# Display_V1_1.net
KiCad netlist of a schematic drawn in EAGLE
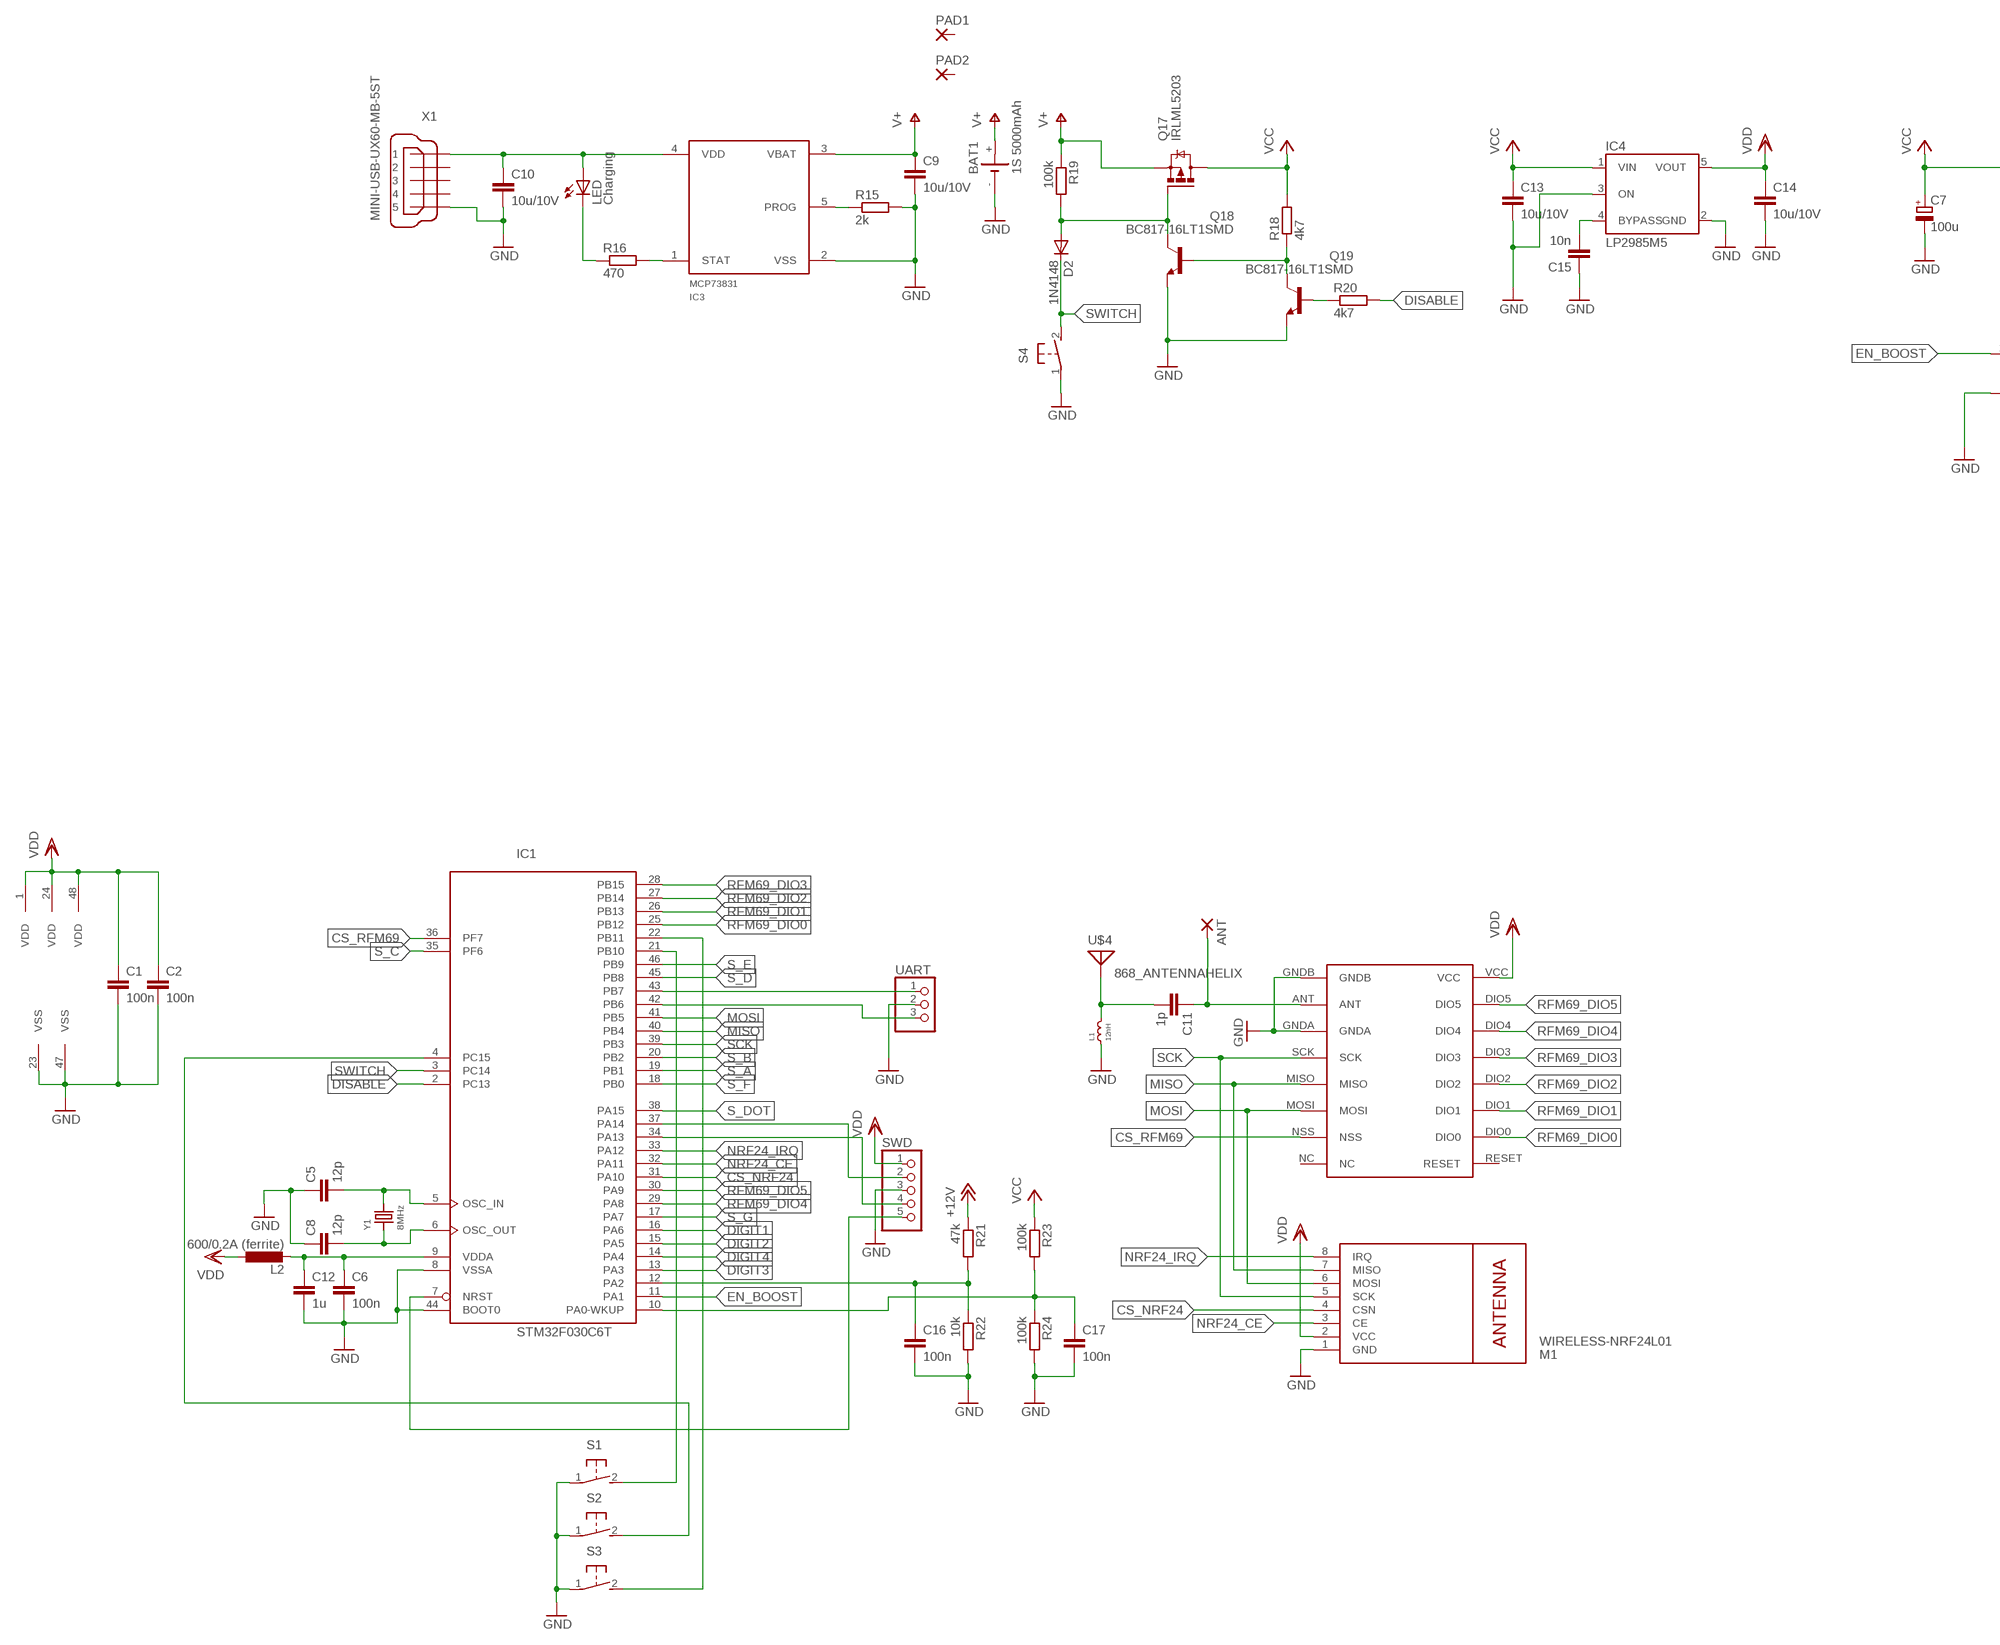
[diagram p0: schematic, sheet 1, part 1 of 2]
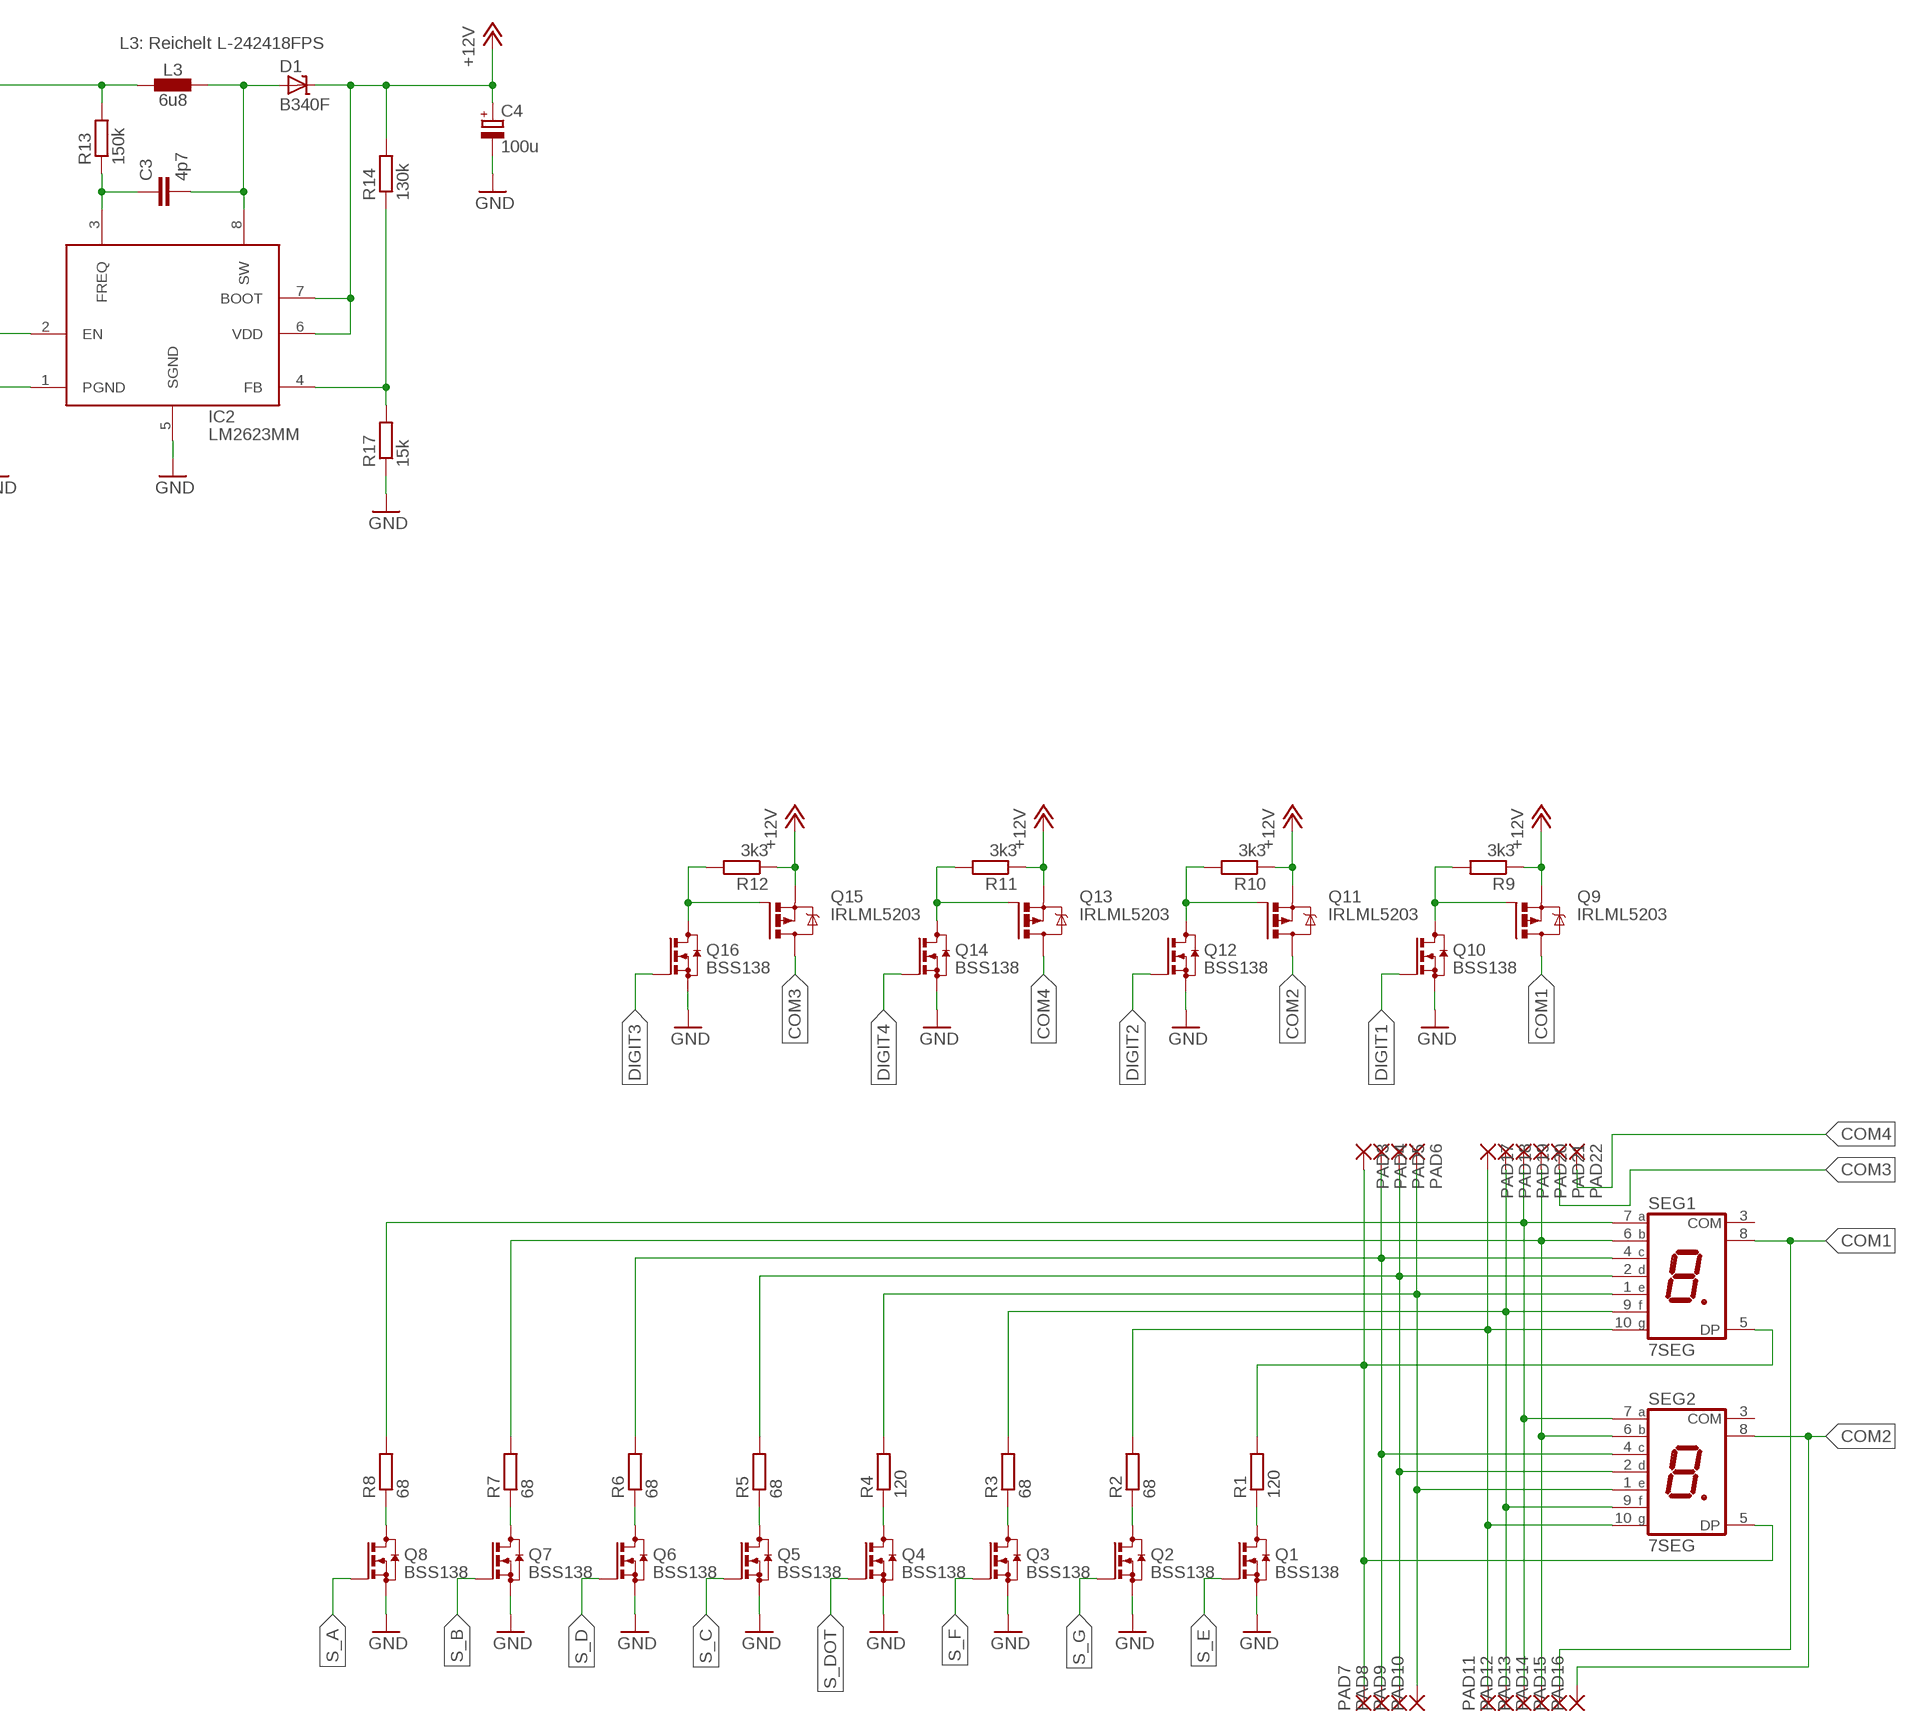
[diagram p1: schematic, sheet 1, part 2 of 2]

(export (version "E")
  (design (tool "Eeschema 10.0.6"))
  (components
    (comp (ref "ANT")
      (value "1,6/0,8")
      (footprint "eagle-import:1,6_0,8")
      (libsource (lib "eagle-import") (part "1,6/0,8"))
    )
    (comp (ref "BAT1")
      (value "1S 5000mAh")
      (footprint "eagle-import:1S_5000MAH")
      (libsource (lib "eagle-import") (part "LIPO"))
    )
    (comp (ref "C1")
      (value "100n")
      (footprint "eagle-import:C0603K")
      (libsource (lib "eagle-import") (part "C-EUC0603K"))
    )
    (comp (ref "C2")
      (value "100n")
      (footprint "eagle-import:C0603K")
      (libsource (lib "eagle-import") (part "C-EUC0603K"))
    )
    (comp (ref "C3")
      (value "4p7")
      (footprint "eagle-import:C0603")
      (libsource (lib "eagle-import") (part "C-EUC0603"))
    )
    (comp (ref "C4")
      (value "100u")
      (footprint "eagle-import:153CLV-0605")
      (libsource (lib "eagle-import") (part "CPOL-EU153CLV-0605"))
    )
    (comp (ref "C5")
      (value "12p")
      (footprint "eagle-import:C0603")
      (libsource (lib "eagle-import") (part "C-EUC0603"))
    )
    (comp (ref "C6")
      (value "100n")
      (footprint "eagle-import:C0603")
      (libsource (lib "eagle-import") (part "C-EUC0603"))
    )
    (comp (ref "C7")
      (value "100u")
      (footprint "eagle-import:153CLV-0605")
      (libsource (lib "eagle-import") (part "CPOL-EU153CLV-0605"))
    )
    (comp (ref "C8")
      (value "12p")
      (footprint "eagle-import:C0603")
      (libsource (lib "eagle-import") (part "C-EUC0603"))
    )
    (comp (ref "C9")
      (value "10u/10V")
      (footprint "eagle-import:C1206")
      (libsource (lib "eagle-import") (part "C-EUC1206"))
    )
    (comp (ref "C10")
      (value "10u/10V")
      (footprint "eagle-import:C1206")
      (libsource (lib "eagle-import") (part "C-EUC1206"))
    )
    (comp (ref "C11")
      (value "1p")
      (footprint "eagle-import:C0603")
      (libsource (lib "eagle-import") (part "C-EUC0603"))
    )
    (comp (ref "C12")
      (value "1u")
      (footprint "eagle-import:C0603")
      (libsource (lib "eagle-import") (part "C-EUC0603"))
    )
    (comp (ref "C13")
      (value "10u/10V")
      (footprint "eagle-import:C1206")
      (libsource (lib "eagle-import") (part "C-EUC1206"))
    )
    (comp (ref "C14")
      (value "10u/10V")
      (footprint "eagle-import:C1206")
      (libsource (lib "eagle-import") (part "C-EUC1206"))
    )
    (comp (ref "C15")
      (value "10n")
      (footprint "eagle-import:C0603")
      (libsource (lib "eagle-import") (part "C-EUC0603"))
    )
    (comp (ref "C16")
      (value "100n")
      (footprint "eagle-import:C0603")
      (libsource (lib "eagle-import") (part "C-EUC0603"))
    )
    (comp (ref "C17")
      (value "100n")
      (footprint "eagle-import:C0603")
      (libsource (lib "eagle-import") (part "C-EUC0603"))
    )
    (comp (ref "D1")
      (value "B340F")
      (footprint "eagle-import:SMC")
      (libsource (lib "eagle-import") (part "SD-SMC"))
    )
    (comp (ref "D2")
      (value "1N4148")
      (footprint "eagle-import:MINIMELF")
      (libsource (lib "eagle-import") (part "DIODE-MINIMELF"))
    )
    (comp (ref "IC1")
      (value "STM32F030C6T")
      (footprint "eagle-import:LQFP48")
      (libsource (lib "eagle-import") (part "STM32F030CT6"))
    )
    (comp (ref "IC2")
      (value "LM2623MM")
      (footprint "eagle-import:MSOP08")
      (libsource (lib "eagle-import") (part "LM2623MM"))
    )
    (comp (ref "IC3")
      (value "MCP73831")
      (footprint "eagle-import:SOT23-5")
      (libsource (lib "eagle-import") (part "MCP73831"))
    )
    (comp (ref "IC4")
      (value "LP2985M5")
      (footprint "eagle-import:SOT23-5")
      (libsource (lib "eagle-import") (part "LP2985M5"))
    )
    (comp (ref "L1")
      (value "12nH")
      (footprint "eagle-import:0603")
      (libsource (lib "eagle-import") (part "RF-INDUCTOR.0603"))
    )
    (comp (ref "L2")
      (value "600/0.2A (ferrite)")
      (footprint "eagle-import:L2012C")
      (libsource (lib "eagle-import") (part "L-EUL2012C"))
    )
    (comp (ref "L3")
      (value "6u8")
      (footprint "eagle-import:L_NR60XX")
      (libsource (lib "eagle-import") (part "INDUCTOR-NR60XX"))
    )
    (comp (ref "LED")
      (value "Charging")
      (footprint "eagle-import:CHIPLED_0603")
      (libsource (lib "eagle-import") (part "LEDCHIPLED_0603"))
    )
    (comp (ref "M1")
      (value "WIRELESS-NRF24L01")
      (footprint "eagle-import:WIRELESS-NRF24L01")
      (libsource (lib "eagle-import") (part "WIRELESS-NRF24L01"))
    )
    (comp (ref "PAD1")
      (value "2,54/1,0")
      (footprint "eagle-import:2,54_1,0")
      (libsource (lib "eagle-import") (part "2,54/1,0"))
    )
    (comp (ref "PAD2")
      (value "2,54/1,0")
      (footprint "eagle-import:2,54_1,0")
      (libsource (lib "eagle-import") (part "2,54/1,0"))
    )
    (comp (ref "PAD3")
      (value "SMD2")
      (footprint "eagle-import:SMD1,27-2,54")
      (libsource (lib "eagle-import") (part "SMD2"))
    )
    (comp (ref "PAD4")
      (value "SMD2")
      (footprint "eagle-import:SMD1,27-2,54")
      (libsource (lib "eagle-import") (part "SMD2"))
    )
    (comp (ref "PAD5")
      (value "SMD2")
      (footprint "eagle-import:SMD1,27-2,54")
      (libsource (lib "eagle-import") (part "SMD2"))
    )
    (comp (ref "PAD6")
      (value "SMD2")
      (footprint "eagle-import:SMD1,27-2,54")
      (libsource (lib "eagle-import") (part "SMD2"))
    )
    (comp (ref "PAD7")
      (value "SMD2")
      (footprint "eagle-import:SMD1,27-2,54")
      (libsource (lib "eagle-import") (part "SMD2"))
    )
    (comp (ref "PAD8")
      (value "SMD2")
      (footprint "eagle-import:SMD1,27-2,54")
      (libsource (lib "eagle-import") (part "SMD2"))
    )
    (comp (ref "PAD9")
      (value "SMD2")
      (footprint "eagle-import:SMD1,27-2,54")
      (libsource (lib "eagle-import") (part "SMD2"))
    )
    (comp (ref "PAD10")
      (value "SMD2")
      (footprint "eagle-import:SMD1,27-2,54")
      (libsource (lib "eagle-import") (part "SMD2"))
    )
    (comp (ref "PAD11")
      (value "SMD2")
      (footprint "eagle-import:SMD1,27-2,54")
      (libsource (lib "eagle-import") (part "SMD2"))
    )
    (comp (ref "PAD12")
      (value "SMD2")
      (footprint "eagle-import:SMD1,27-2,54")
      (libsource (lib "eagle-import") (part "SMD2"))
    )
    (comp (ref "PAD13")
      (value "SMD2")
      (footprint "eagle-import:SMD1,27-2,54")
      (libsource (lib "eagle-import") (part "SMD2"))
    )
    (comp (ref "PAD14")
      (value "SMD2")
      (footprint "eagle-import:SMD1,27-2,54")
      (libsource (lib "eagle-import") (part "SMD2"))
    )
    (comp (ref "PAD15")
      (value "SMD2")
      (footprint "eagle-import:SMD1,27-2,54")
      (libsource (lib "eagle-import") (part "SMD2"))
    )
    (comp (ref "PAD16")
      (value "SMD2")
      (footprint "eagle-import:SMD1,27-2,54")
      (libsource (lib "eagle-import") (part "SMD2"))
    )
    (comp (ref "PAD17")
      (value "SMD2")
      (footprint "eagle-import:SMD1,27-2,54")
      (libsource (lib "eagle-import") (part "SMD2"))
    )
    (comp (ref "PAD18")
      (value "SMD2")
      (footprint "eagle-import:SMD1,27-2,54")
      (libsource (lib "eagle-import") (part "SMD2"))
    )
    (comp (ref "PAD19")
      (value "SMD2")
      (footprint "eagle-import:SMD1,27-2,54")
      (libsource (lib "eagle-import") (part "SMD2"))
    )
    (comp (ref "PAD20")
      (value "SMD2")
      (footprint "eagle-import:SMD1,27-2,54")
      (libsource (lib "eagle-import") (part "SMD2"))
    )
    (comp (ref "PAD21")
      (value "SMD2")
      (footprint "eagle-import:SMD1,27-2,54")
      (libsource (lib "eagle-import") (part "SMD2"))
    )
    (comp (ref "PAD22")
      (value "SMD2")
      (footprint "eagle-import:SMD1,27-2,54")
      (libsource (lib "eagle-import") (part "SMD2"))
    )
    (comp (ref "Q1")
      (value "BSS138")
      (footprint "eagle-import:SOT23")
      (libsource (lib "eagle-import") (part "BSS123"))
    )
    (comp (ref "Q2")
      (value "BSS138")
      (footprint "eagle-import:SOT23")
      (libsource (lib "eagle-import") (part "BSS123"))
    )
    (comp (ref "Q3")
      (value "BSS138")
      (footprint "eagle-import:SOT23")
      (libsource (lib "eagle-import") (part "BSS123"))
    )
    (comp (ref "Q4")
      (value "BSS138")
      (footprint "eagle-import:SOT23")
      (libsource (lib "eagle-import") (part "BSS123"))
    )
    (comp (ref "Q5")
      (value "BSS138")
      (footprint "eagle-import:SOT23")
      (libsource (lib "eagle-import") (part "BSS123"))
    )
    (comp (ref "Q6")
      (value "BSS138")
      (footprint "eagle-import:SOT23")
      (libsource (lib "eagle-import") (part "BSS123"))
    )
    (comp (ref "Q7")
      (value "BSS138")
      (footprint "eagle-import:SOT23")
      (libsource (lib "eagle-import") (part "BSS123"))
    )
    (comp (ref "Q8")
      (value "BSS138")
      (footprint "eagle-import:SOT23")
      (libsource (lib "eagle-import") (part "BSS123"))
    )
    (comp (ref "Q9")
      (value "IRLML5203")
      (footprint "eagle-import:MICRO3")
      (libsource (lib "eagle-import") (part "IRLML5203"))
    )
    (comp (ref "Q10")
      (value "BSS138")
      (footprint "eagle-import:SOT23")
      (libsource (lib "eagle-import") (part "BSS123"))
    )
    (comp (ref "Q11")
      (value "IRLML5203")
      (footprint "eagle-import:MICRO3")
      (libsource (lib "eagle-import") (part "IRLML5203"))
    )
    (comp (ref "Q12")
      (value "BSS138")
      (footprint "eagle-import:SOT23")
      (libsource (lib "eagle-import") (part "BSS123"))
    )
    (comp (ref "Q13")
      (value "IRLML5203")
      (footprint "eagle-import:MICRO3")
      (libsource (lib "eagle-import") (part "IRLML5203"))
    )
    (comp (ref "Q14")
      (value "BSS138")
      (footprint "eagle-import:SOT23")
      (libsource (lib "eagle-import") (part "BSS123"))
    )
    (comp (ref "Q15")
      (value "IRLML5203")
      (footprint "eagle-import:MICRO3")
      (libsource (lib "eagle-import") (part "IRLML5203"))
    )
    (comp (ref "Q16")
      (value "BSS138")
      (footprint "eagle-import:SOT23")
      (libsource (lib "eagle-import") (part "BSS123"))
    )
    (comp (ref "Q17")
      (value "IRLML5203")
      (footprint "eagle-import:MICRO3")
      (libsource (lib "eagle-import") (part "IRLML5203"))
    )
    (comp (ref "Q18")
      (value "BC817-16LT1SMD")
      (footprint "eagle-import:SOT23-BEC")
      (libsource (lib "eagle-import") (part "BC817SMD-16LT1"))
    )
    (comp (ref "Q19")
      (value "BC817-16LT1SMD")
      (footprint "eagle-import:SOT23-BEC")
      (libsource (lib "eagle-import") (part "BC817SMD-16LT1"))
    )
    (comp (ref "R1")
      (value "120")
      (footprint "eagle-import:R1206")
      (libsource (lib "eagle-import") (part "R-EU_R1206"))
    )
    (comp (ref "R2")
      (value "68")
      (footprint "eagle-import:R1206")
      (libsource (lib "eagle-import") (part "R-EU_R1206"))
    )
    (comp (ref "R3")
      (value "68")
      (footprint "eagle-import:R1206")
      (libsource (lib "eagle-import") (part "R-EU_R1206"))
    )
    (comp (ref "R4")
      (value "120")
      (footprint "eagle-import:R1206")
      (libsource (lib "eagle-import") (part "R-EU_R1206"))
    )
    (comp (ref "R5")
      (value "68")
      (footprint "eagle-import:R1206")
      (libsource (lib "eagle-import") (part "R-EU_R1206"))
    )
    (comp (ref "R6")
      (value "68")
      (footprint "eagle-import:R1206")
      (libsource (lib "eagle-import") (part "R-EU_R1206"))
    )
    (comp (ref "R7")
      (value "68")
      (footprint "eagle-import:R1206")
      (libsource (lib "eagle-import") (part "R-EU_R1206"))
    )
    (comp (ref "R8")
      (value "68")
      (footprint "eagle-import:R1206")
      (libsource (lib "eagle-import") (part "R-EU_R1206"))
    )
    (comp (ref "R9")
      (value "3k3")
      (footprint "eagle-import:R0603")
      (libsource (lib "eagle-import") (part "resistor_R-EU_R0603"))
    )
    (comp (ref "R10")
      (value "3k3")
      (footprint "eagle-import:R0603")
      (libsource (lib "eagle-import") (part "resistor_R-EU_R0603"))
    )
    (comp (ref "R11")
      (value "3k3")
      (footprint "eagle-import:R0603")
      (libsource (lib "eagle-import") (part "resistor_R-EU_R0603"))
    )
    (comp (ref "R12")
      (value "3k3")
      (footprint "eagle-import:R0603")
      (libsource (lib "eagle-import") (part "resistor_R-EU_R0603"))
    )
    (comp (ref "R13")
      (value "150k")
      (footprint "eagle-import:R0603")
      (libsource (lib "eagle-import") (part "R-EU_R0603"))
    )
    (comp (ref "R14")
      (value "130k")
      (footprint "eagle-import:R0603")
      (libsource (lib "eagle-import") (part "R-EU_R0603"))
    )
    (comp (ref "R15")
      (value "2k")
      (footprint "eagle-import:R0603")
      (libsource (lib "eagle-import") (part "R-EU_R0603"))
    )
    (comp (ref "R16")
      (value "470")
      (footprint "eagle-import:R0603")
      (libsource (lib "eagle-import") (part "R-EU_R0603"))
    )
    (comp (ref "R17")
      (value "15k")
      (footprint "eagle-import:R0603")
      (libsource (lib "eagle-import") (part "R-EU_R0603"))
    )
    (comp (ref "R18")
      (value "4k7")
      (footprint "eagle-import:R0603")
      (libsource (lib "eagle-import") (part "R-EU_R0603"))
    )
    (comp (ref "R19")
      (value "100k")
      (footprint "eagle-import:R0603")
      (libsource (lib "eagle-import") (part "R-EU_R0603"))
    )
    (comp (ref "R20")
      (value "4k7")
      (footprint "eagle-import:R0603")
      (libsource (lib "eagle-import") (part "R-EU_R0603"))
    )
    (comp (ref "R21")
      (value "47k")
      (footprint "eagle-import:R0603")
      (libsource (lib "eagle-import") (part "R-EU_R0603"))
    )
    (comp (ref "R22")
      (value "10k")
      (footprint "eagle-import:R0603")
      (libsource (lib "eagle-import") (part "R-EU_R0603"))
    )
    (comp (ref "R23")
      (value "100k")
      (footprint "eagle-import:R0603")
      (libsource (lib "eagle-import") (part "R-EU_R0603"))
    )
    (comp (ref "R24")
      (value "100k")
      (footprint "eagle-import:R0603")
      (libsource (lib "eagle-import") (part "R-EU_R0603"))
    )
    (comp (ref "S1")
      (value "31-XX")
      (footprint "eagle-import:B3F-31XX")
      (fields (field (name "MPN") "B3F-3100"))
      (libsource (lib "eagle-import") (part "31-XX"))
    )
    (comp (ref "S2")
      (value "31-XX")
      (footprint "eagle-import:B3F-31XX")
      (fields (field (name "MPN") "B3F-3100"))
      (libsource (lib "eagle-import") (part "31-XX"))
    )
    (comp (ref "S3")
      (value "31-XX")
      (footprint "eagle-import:B3F-31XX")
      (fields (field (name "MPN") "B3F-3100"))
      (libsource (lib "eagle-import") (part "31-XX"))
    )
    (comp (ref "S4")
      (value "31-XX")
      (footprint "eagle-import:B3F-31XX")
      (fields (field (name "MPN") "B3F-3100"))
      (libsource (lib "eagle-import") (part "31-XX"))
    )
    (comp (ref "SEG1")
      (value "7SEG")
      (footprint "eagle-import:7SEG_70_40")
      (libsource (lib "eagle-import") (part "7SEG"))
    )
    (comp (ref "SEG2")
      (value "7SEG")
      (footprint "eagle-import:7SEG_70_40")
      (libsource (lib "eagle-import") (part "7SEG"))
    )
    (comp (ref "SWD")
      (value "PINHD-1X5")
      (footprint "eagle-import:1X05")
      (libsource (lib "eagle-import") (part "PINHD-1X5"))
    )
    (comp (ref "U$1")
      (value "RFM69HW")
      (footprint "eagle-import:RFM")
      (libsource (lib "eagle-import") (part "RFM69HW"))
    )
    (comp (ref "U$4")
      (value "868_ANTENNAHELIX")
      (footprint "eagle-import:HELIX_868")
      (libsource (lib "eagle-import") (part "868_ANTENNAHELIX"))
    )
    (comp (ref "UART")
      (value "PINHD-1X3")
      (footprint "eagle-import:1X03")
      (libsource (lib "eagle-import") (part "PINHD-1X3"))
    )
    (comp (ref "X1")
      (value "MINI-USB-UX60-MB-5ST")
      (footprint "eagle-import:UX60-MB-5ST")
      (libsource (lib "eagle-import") (part "MINI-USB-UX60-MB-5ST"))
    )
    (comp (ref "Y1")
      (value "8MHz")
      (footprint "eagle-import:3.2X2.5MM")
      (libsource (lib "eagle-import") (part "CRYSTAL.3.2X2.5MM"))
    )
  )
  (nets
    (net (code "1") (name "+12V") (class "Default")
      (node (ref "C4") (pin "+") (pinfunction "+_+") (pintype "passive"))
      (node (ref "D1") (pin "C") (pinfunction "C_C") (pintype "passive"))
      (node (ref "IC2") (pin "6") (pinfunction "VDD_6") (pintype "bidirectional"))
      (node (ref "IC2") (pin "7") (pinfunction "BOOT_7") (pintype "bidirectional"))
      (node (ref "Q11") (pin "2") (pinfunction "S_2") (pintype "passive"))
      (node (ref "Q13") (pin "2") (pinfunction "S_2") (pintype "passive"))
      (node (ref "Q15") (pin "2") (pinfunction "S_2") (pintype "passive"))
      (node (ref "Q9") (pin "2") (pinfunction "S_2") (pintype "passive"))
      (node (ref "R10") (pin "1") (pinfunction "1_1") (pintype "passive"))
      (node (ref "R11") (pin "1") (pinfunction "1_1") (pintype "passive"))
      (node (ref "R12") (pin "1") (pinfunction "1_1") (pintype "passive"))
      (node (ref "R14") (pin "2") (pinfunction "2_2") (pintype "passive"))
      (node (ref "R21") (pin "1") (pinfunction "1_1") (pintype "passive"))
      (node (ref "R9") (pin "1") (pinfunction "1_1") (pintype "passive"))
    )
    (net (code "2") (name "COM1") (class "Default")
      (node (ref "PAD15") (pin "1") (pinfunction "P_1") (pintype "passive"))
      (node (ref "Q9") (pin "3") (pinfunction "D_3") (pintype "passive"))
      (node (ref "SEG1") (pin "8") (pinfunction "COM_8") (pintype "passive"))
    )
    (net (code "3") (name "COM2") (class "Default")
      (node (ref "PAD16") (pin "1") (pinfunction "P_1") (pintype "passive"))
      (node (ref "Q11") (pin "3") (pinfunction "D_3") (pintype "passive"))
      (node (ref "SEG2") (pin "8") (pinfunction "COM_8") (pintype "passive"))
    )
    (net (code "4") (name "COM3") (class "Default")
      (node (ref "PAD21") (pin "1") (pinfunction "P_1") (pintype "passive"))
      (node (ref "Q15") (pin "3") (pinfunction "D_3") (pintype "passive"))
    )
    (net (code "5") (name "COM4") (class "Default")
      (node (ref "PAD22") (pin "1") (pinfunction "P_1") (pintype "passive"))
      (node (ref "Q13") (pin "3") (pinfunction "D_3") (pintype "passive"))
    )
    (net (code "6") (name "CS_NRF24") (class "Default")
      (node (ref "IC1") (pin "31") (pinfunction "PA10_31") (pintype "bidirectional"))
      (node (ref "M1") (pin "4") (pinfunction "CSN_4") (pintype "bidirectional"))
    )
    (net (code "7") (name "CS_RFM69") (class "Default")
      (node (ref "IC1") (pin "36") (pinfunction "PF7_36") (pintype "bidirectional"))
      (node (ref "U$1") (pin "NSS") (pinfunction "NSS_NSS") (pintype "bidirectional"))
    )
    (net (code "8") (name "DIGIT1") (class "Default")
      (node (ref "IC1") (pin "16") (pinfunction "PA6_16") (pintype "bidirectional"))
      (node (ref "Q10") (pin "1") (pinfunction "G_1") (pintype "passive"))
    )
    (net (code "9") (name "DIGIT2") (class "Default")
      (node (ref "IC1") (pin "15") (pinfunction "PA5_15") (pintype "bidirectional"))
      (node (ref "Q12") (pin "1") (pinfunction "G_1") (pintype "passive"))
    )
    (net (code "10") (name "DIGIT3") (class "Default")
      (node (ref "IC1") (pin "13") (pinfunction "PA3_13") (pintype "bidirectional"))
      (node (ref "Q16") (pin "1") (pinfunction "G_1") (pintype "passive"))
    )
    (net (code "11") (name "DIGIT4") (class "Default")
      (node (ref "IC1") (pin "14") (pinfunction "PA4_14") (pintype "bidirectional"))
      (node (ref "Q14") (pin "1") (pinfunction "G_1") (pintype "passive"))
    )
    (net (code "12") (name "DISABLE") (class "Default")
      (node (ref "IC1") (pin "2") (pinfunction "PC13_2") (pintype "bidirectional"))
      (node (ref "R20") (pin "2") (pinfunction "2_2") (pintype "passive"))
    )
    (net (code "13") (name "EN_BOOST") (class "Default")
      (node (ref "IC1") (pin "11") (pinfunction "PA1_11") (pintype "bidirectional"))
      (node (ref "IC2") (pin "2") (pinfunction "EN_2") (pintype "bidirectional"))
    )
    (net (code "14") (name "GND") (class "Default")
      (node (ref "BAT1") (pin "-") (pinfunction "-_-") (pintype "passive"))
      (node (ref "C1") (pin "2") (pinfunction "2_2") (pintype "passive"))
      (node (ref "C10") (pin "2") (pinfunction "2_2") (pintype "passive"))
      (node (ref "C12") (pin "2") (pinfunction "2_2") (pintype "passive"))
      (node (ref "C13") (pin "2") (pinfunction "2_2") (pintype "passive"))
      (node (ref "C14") (pin "2") (pinfunction "2_2") (pintype "passive"))
      (node (ref "C15") (pin "1") (pinfunction "1_1") (pintype "passive"))
      (node (ref "C16") (pin "2") (pinfunction "2_2") (pintype "passive"))
      (node (ref "C17") (pin "2") (pinfunction "2_2") (pintype "passive"))
      (node (ref "C2") (pin "2") (pinfunction "2_2") (pintype "passive"))
      (node (ref "C4") (pin "-") (pinfunction "-_-") (pintype "passive"))
      (node (ref "C5") (pin "1") (pinfunction "1_1") (pintype "passive"))
      (node (ref "C6") (pin "2") (pinfunction "2_2") (pintype "passive"))
      (node (ref "C7") (pin "-") (pinfunction "-_-") (pintype "passive"))
      (node (ref "C8") (pin "1") (pinfunction "1_1") (pintype "passive"))
      (node (ref "C9") (pin "2") (pinfunction "2_2") (pintype "passive"))
      (node (ref "IC1") (pin "23") (pinfunction "VSS_23") (pintype "power_in"))
      (node (ref "IC1") (pin "44") (pinfunction "BOOT0_44") (pintype "input"))
      (node (ref "IC1") (pin "47") (pinfunction "VSS_47") (pintype "power_in"))
      (node (ref "IC1") (pin "8") (pinfunction "VSSA_8") (pintype "power_in"))
      (node (ref "IC2") (pin "1") (pinfunction "PGND_1") (pintype "bidirectional"))
      (node (ref "IC2") (pin "5") (pinfunction "SGND_5") (pintype "bidirectional"))
      (node (ref "IC3") (pin "2") (pinfunction "VSS_2") (pintype "bidirectional"))
      (node (ref "IC4") (pin "2") (pinfunction "GND_2") (pintype "power_in"))
      (node (ref "IC4") (pin "3") (pinfunction "ON_3") (pintype "input"))
      (node (ref "L1") (pin "1") (pinfunction "1_1") (pintype "passive"))
      (node (ref "M1") (pin "1") (pinfunction "GND_1") (pintype "power_in"))
      (node (ref "Q1") (pin "2") (pinfunction "S_2") (pintype "passive"))
      (node (ref "Q10") (pin "2") (pinfunction "S_2") (pintype "passive"))
      (node (ref "Q12") (pin "2") (pinfunction "S_2") (pintype "passive"))
      (node (ref "Q14") (pin "2") (pinfunction "S_2") (pintype "passive"))
      (node (ref "Q16") (pin "2") (pinfunction "S_2") (pintype "passive"))
      (node (ref "Q18") (pin "E") (pinfunction "E_E") (pintype "passive"))
      (node (ref "Q19") (pin "E") (pinfunction "E_E") (pintype "passive"))
      (node (ref "Q2") (pin "2") (pinfunction "S_2") (pintype "passive"))
      (node (ref "Q3") (pin "2") (pinfunction "S_2") (pintype "passive"))
      (node (ref "Q4") (pin "2") (pinfunction "S_2") (pintype "passive"))
      (node (ref "Q5") (pin "2") (pinfunction "S_2") (pintype "passive"))
      (node (ref "Q6") (pin "2") (pinfunction "S_2") (pintype "passive"))
      (node (ref "Q7") (pin "2") (pinfunction "S_2") (pintype "passive"))
      (node (ref "Q8") (pin "2") (pinfunction "S_2") (pintype "passive"))
      (node (ref "R15") (pin "2") (pinfunction "2_2") (pintype "passive"))
      (node (ref "R17") (pin "1") (pinfunction "1_1") (pintype "passive"))
      (node (ref "R22") (pin "2") (pinfunction "2_2") (pintype "passive"))
      (node (ref "R24") (pin "2") (pinfunction "2_2") (pintype "passive"))
      (node (ref "S1") (pin "1") (pinfunction "P_1") (pintype "passive"))
      (node (ref "S2") (pin "1") (pinfunction "P_1") (pintype "passive"))
      (node (ref "S3") (pin "1") (pinfunction "P_1") (pintype "passive"))
      (node (ref "S4") (pin "1") (pinfunction "P_1") (pintype "passive"))
      (node (ref "SWD") (pin "3") (pinfunction "3_3") (pintype "passive"))
      (node (ref "U$1") (pin "GNDA") (pinfunction "GNDA_GNDA") (pintype "bidirectional"))
      (node (ref "U$1") (pin "GNDB") (pinfunction "GNDB_GNDB") (pintype "bidirectional"))
      (node (ref "UART") (pin "2") (pinfunction "2_2") (pintype "passive"))
      (node (ref "X1") (pin "5") (pinfunction "5_5") (pintype "input"))
    )
    (net (code "15") (name "MISO") (class "Default")
      (node (ref "IC1") (pin "40") (pinfunction "PB4_40") (pintype "bidirectional"))
      (node (ref "M1") (pin "7") (pinfunction "MISO_7") (pintype "bidirectional"))
      (node (ref "U$1") (pin "MISO") (pinfunction "MISO_MISO") (pintype "bidirectional"))
    )
    (net (code "16") (name "MOSI") (class "Default")
      (node (ref "IC1") (pin "41") (pinfunction "PB5_41") (pintype "bidirectional"))
      (node (ref "M1") (pin "6") (pinfunction "MOSI_6") (pintype "bidirectional"))
      (node (ref "U$1") (pin "MOSI") (pinfunction "MOSI_MOSI") (pintype "bidirectional"))
    )
    (net (code "17") (name "NRF24_CE") (class "Default")
      (node (ref "IC1") (pin "32") (pinfunction "PA11_32") (pintype "bidirectional"))
      (node (ref "M1") (pin "3") (pinfunction "CE_3") (pintype "bidirectional"))
    )
    (net (code "18") (name "NRF24_IRQ") (class "Default")
      (node (ref "IC1") (pin "33") (pinfunction "PA12_33") (pintype "bidirectional"))
      (node (ref "M1") (pin "8") (pinfunction "IRQ_8") (pintype "bidirectional"))
    )
    (net (code "19") (name "Net-(ANT-P)") (class "Default")
      (node (ref "ANT") (pin "1") (pinfunction "P_1") (pintype "passive"))
      (node (ref "C11") (pin "1") (pinfunction "1_1") (pintype "passive"))
      (node (ref "U$1") (pin "ANT") (pinfunction "ANT_ANT") (pintype "bidirectional"))
    )
    (net (code "20") (name "Net-(C11-Pad2)") (class "Default")
      (node (ref "C11") (pin "2") (pinfunction "2_2") (pintype "passive"))
      (node (ref "L1") (pin "2") (pinfunction "2_2") (pintype "passive"))
      (node (ref "U$4") (pin "ANT") (pinfunction "1_ANT") (pintype "output"))
      (node (ref "U$4") (pin "P$10") (pinfunction "1_P$10") (pintype "output"))
      (node (ref "U$4") (pin "P$11") (pinfunction "1_P$11") (pintype "output"))
      (node (ref "U$4") (pin "P$12") (pinfunction "1_P$12") (pintype "output"))
      (node (ref "U$4") (pin "P$13") (pinfunction "1_P$13") (pintype "output"))
      (node (ref "U$4") (pin "P$14") (pinfunction "1_P$14") (pintype "output"))
      (node (ref "U$4") (pin "P$15") (pinfunction "1_P$15") (pintype "output"))
      (node (ref "U$4") (pin "P$16") (pinfunction "1_P$16") (pintype "output"))
      (node (ref "U$4") (pin "P$17") (pinfunction "1_P$17") (pintype "output"))
      (node (ref "U$4") (pin "P$18") (pinfunction "1_P$18") (pintype "output"))
      (node (ref "U$4") (pin "P$19") (pinfunction "1_P$19") (pintype "output"))
      (node (ref "U$4") (pin "P$2") (pinfunction "1_P$2") (pintype "output"))
      (node (ref "U$4") (pin "P$20") (pinfunction "1_P$20") (pintype "output"))
      (node (ref "U$4") (pin "P$3") (pinfunction "1_P$3") (pintype "output"))
      (node (ref "U$4") (pin "P$4") (pinfunction "1_P$4") (pintype "output"))
      (node (ref "U$4") (pin "P$5") (pinfunction "1_P$5") (pintype "output"))
      (node (ref "U$4") (pin "P$6") (pinfunction "1_P$6") (pintype "output"))
      (node (ref "U$4") (pin "P$7") (pinfunction "1_P$7") (pintype "output"))
      (node (ref "U$4") (pin "P$8") (pinfunction "1_P$8") (pintype "output"))
      (node (ref "U$4") (pin "P$9") (pinfunction "1_P$9") (pintype "output"))
    )
    (net (code "21") (name "Net-(IC1A-NRST)") (class "Default")
      (node (ref "IC1") (pin "7") (pinfunction "NRST_7") (pintype "bidirectional"))
      (node (ref "SWD") (pin "5") (pinfunction "5_5") (pintype "passive"))
    )
    (net (code "22") (name "Net-(IC1A-OSC_IN)") (class "Default")
      (node (ref "C5") (pin "2") (pinfunction "2_2") (pintype "passive"))
      (node (ref "IC1") (pin "5") (pinfunction "OSC_IN_5") (pintype "bidirectional"))
      (node (ref "Y1") (pin "3") (pinfunction "2_3") (pintype "passive"))
    )
    (net (code "23") (name "Net-(IC1A-OSC_OUT)") (class "Default")
      (node (ref "C8") (pin "2") (pinfunction "2_2") (pintype "passive"))
      (node (ref "IC1") (pin "6") (pinfunction "OSC_OUT_6") (pintype "bidirectional"))
      (node (ref "Y1") (pin "1") (pinfunction "1_1") (pintype "passive"))
    )
    (net (code "24") (name "Net-(IC1A-PA0-WKUP)") (class "Default")
      (node (ref "C17") (pin "1") (pinfunction "1_1") (pintype "passive"))
      (node (ref "IC1") (pin "10") (pinfunction "PA0-WKUP_10") (pintype "bidirectional"))
      (node (ref "R23") (pin "2") (pinfunction "2_2") (pintype "passive"))
      (node (ref "R24") (pin "1") (pinfunction "1_1") (pintype "passive"))
    )
    (net (code "25") (name "Net-(IC1A-PA2)") (class "Default")
      (node (ref "C16") (pin "1") (pinfunction "1_1") (pintype "passive"))
      (node (ref "IC1") (pin "12") (pinfunction "PA2_12") (pintype "bidirectional"))
      (node (ref "R21") (pin "2") (pinfunction "2_2") (pintype "passive"))
      (node (ref "R22") (pin "1") (pinfunction "1_1") (pintype "passive"))
    )
    (net (code "26") (name "Net-(IC1A-PA13)") (class "Default")
      (node (ref "IC1") (pin "34") (pinfunction "PA13_34") (pintype "bidirectional"))
      (node (ref "SWD") (pin "4") (pinfunction "4_4") (pintype "passive"))
    )
    (net (code "27") (name "Net-(IC1A-PA14)") (class "Default")
      (node (ref "IC1") (pin "37") (pinfunction "PA14_37") (pintype "bidirectional"))
      (node (ref "SWD") (pin "2") (pinfunction "2_2") (pintype "passive"))
    )
    (net (code "28") (name "Net-(IC1A-PB6)") (class "Default")
      (node (ref "IC1") (pin "42") (pinfunction "PB6_42") (pintype "bidirectional"))
      (node (ref "UART") (pin "3") (pinfunction "3_3") (pintype "passive"))
    )
    (net (code "29") (name "Net-(IC1A-PB7)") (class "Default")
      (node (ref "IC1") (pin "43") (pinfunction "PB7_43") (pintype "bidirectional"))
      (node (ref "UART") (pin "1") (pinfunction "1_1") (pintype "passive"))
    )
    (net (code "30") (name "Net-(IC1A-PB10)") (class "Default")
      (node (ref "IC1") (pin "21") (pinfunction "PB10_21") (pintype "bidirectional"))
      (node (ref "S1") (pin "2") (pinfunction "S_2") (pintype "passive"))
    )
    (net (code "31") (name "Net-(IC1A-PB11)") (class "Default")
      (node (ref "IC1") (pin "22") (pinfunction "PB11_22") (pintype "bidirectional"))
      (node (ref "S3") (pin "2") (pinfunction "S_2") (pintype "passive"))
    )
    (net (code "32") (name "Net-(IC1A-PC15)") (class "Default")
      (node (ref "IC1") (pin "4") (pinfunction "PC15_4") (pintype "bidirectional"))
      (node (ref "S2") (pin "2") (pinfunction "S_2") (pintype "passive"))
    )
    (net (code "33") (name "Net-(IC1A-VDDA)") (class "Default")
      (node (ref "C12") (pin "1") (pinfunction "1_1") (pintype "passive"))
      (node (ref "C6") (pin "1") (pinfunction "1_1") (pintype "passive"))
      (node (ref "IC1") (pin "9") (pinfunction "VDDA_9") (pintype "power_in"))
      (node (ref "L2") (pin "2") (pinfunction "2_2") (pintype "passive"))
    )
    (net (code "34") (name "Net-(IC2-FB)") (class "Default")
      (node (ref "IC2") (pin "4") (pinfunction "FB_4") (pintype "bidirectional"))
      (node (ref "R14") (pin "1") (pinfunction "1_1") (pintype "passive"))
      (node (ref "R17") (pin "2") (pinfunction "2_2") (pintype "passive"))
    )
    (net (code "35") (name "Net-(IC2-FREQ)") (class "Default")
      (node (ref "C3") (pin "1") (pinfunction "1_1") (pintype "passive"))
      (node (ref "IC2") (pin "3") (pinfunction "FREQ_3") (pintype "bidirectional"))
      (node (ref "R13") (pin "1") (pinfunction "1_1") (pintype "passive"))
    )
    (net (code "36") (name "Net-(IC2-SW)") (class "Default")
      (node (ref "C3") (pin "2") (pinfunction "2_2") (pintype "passive"))
      (node (ref "D1") (pin "A") (pinfunction "A_A") (pintype "passive"))
      (node (ref "IC2") (pin "8") (pinfunction "SW_8") (pintype "bidirectional"))
      (node (ref "L3") (pin "2") (pinfunction "2_2") (pintype "passive"))
    )
    (net (code "37") (name "Net-(IC3-PROG)") (class "Default")
      (node (ref "IC3") (pin "5") (pinfunction "PROG_5") (pintype "bidirectional"))
      (node (ref "R15") (pin "1") (pinfunction "1_1") (pintype "passive"))
    )
    (net (code "38") (name "Net-(IC3-STAT)") (class "Default")
      (node (ref "IC3") (pin "1") (pinfunction "STAT_1") (pintype "bidirectional"))
      (node (ref "R16") (pin "2") (pinfunction "2_2") (pintype "passive"))
    )
    (net (code "39") (name "Net-(IC3-VDD)") (class "Default")
      (node (ref "C10") (pin "1") (pinfunction "1_1") (pintype "passive"))
      (node (ref "IC3") (pin "4") (pinfunction "VDD_4") (pintype "bidirectional"))
      (node (ref "LED") (pin "A") (pinfunction "A_A") (pintype "passive"))
      (node (ref "X1") (pin "1") (pinfunction "1_1") (pintype "input"))
    )
    (net (code "40") (name "Net-(IC4-BYPASS)") (class "Default")
      (node (ref "C15") (pin "2") (pinfunction "2_2") (pintype "passive"))
      (node (ref "IC4") (pin "4") (pinfunction "BYPASS_4") (pintype "passive"))
    )
    (net (code "41") (name "Net-(LED-PadC)") (class "Default")
      (node (ref "LED") (pin "C") (pinfunction "C_C") (pintype "passive"))
      (node (ref "R16") (pin "1") (pinfunction "1_1") (pintype "passive"))
    )
    (net (code "42") (name "Net-(PAD3-P)") (class "Default")
      (node (ref "PAD3") (pin "1") (pinfunction "P_1") (pintype "passive"))
      (node (ref "PAD7") (pin "1") (pinfunction "P_1") (pintype "passive"))
      (node (ref "R1") (pin "2") (pinfunction "2_2") (pintype "passive"))
      (node (ref "SEG1") (pin "5") (pinfunction "DP_5") (pintype "passive"))
      (node (ref "SEG2") (pin "5") (pinfunction "DP_5") (pintype "passive"))
    )
    (net (code "43") (name "Net-(PAD4-P)") (class "Default")
      (node (ref "PAD4") (pin "1") (pinfunction "P_1") (pintype "passive"))
      (node (ref "PAD8") (pin "1") (pinfunction "P_1") (pintype "passive"))
      (node (ref "R6") (pin "2") (pinfunction "2_2") (pintype "passive"))
      (node (ref "SEG1") (pin "4") (pinfunction "C_4") (pintype "passive"))
      (node (ref "SEG2") (pin "4") (pinfunction "C_4") (pintype "passive"))
    )
    (net (code "44") (name "Net-(PAD5-P)") (class "Default")
      (node (ref "PAD5") (pin "1") (pinfunction "P_1") (pintype "passive"))
      (node (ref "PAD9") (pin "1") (pinfunction "P_1") (pintype "passive"))
      (node (ref "R5") (pin "2") (pinfunction "2_2") (pintype "passive"))
      (node (ref "SEG1") (pin "2") (pinfunction "D_2") (pintype "passive"))
      (node (ref "SEG2") (pin "2") (pinfunction "D_2") (pintype "passive"))
    )
    (net (code "45") (name "Net-(PAD10-P)") (class "Default")
      (node (ref "PAD10") (pin "1") (pinfunction "P_1") (pintype "passive"))
      (node (ref "PAD6") (pin "1") (pinfunction "P_1") (pintype "passive"))
      (node (ref "R4") (pin "2") (pinfunction "2_2") (pintype "passive"))
      (node (ref "SEG1") (pin "1") (pinfunction "E_1") (pintype "passive"))
      (node (ref "SEG2") (pin "1") (pinfunction "E_1") (pintype "passive"))
    )
    (net (code "46") (name "Net-(PAD11-P)") (class "Default")
      (node (ref "PAD11") (pin "1") (pinfunction "P_1") (pintype "passive"))
      (node (ref "PAD17") (pin "1") (pinfunction "P_1") (pintype "passive"))
      (node (ref "R2") (pin "2") (pinfunction "2_2") (pintype "passive"))
      (node (ref "SEG1") (pin "10") (pinfunction "G_10") (pintype "passive"))
      (node (ref "SEG2") (pin "10") (pinfunction "G_10") (pintype "passive"))
    )
    (net (code "47") (name "Net-(PAD12-P)") (class "Default")
      (node (ref "PAD12") (pin "1") (pinfunction "P_1") (pintype "passive"))
      (node (ref "PAD18") (pin "1") (pinfunction "P_1") (pintype "passive"))
      (node (ref "R3") (pin "2") (pinfunction "2_2") (pintype "passive"))
      (node (ref "SEG1") (pin "9") (pinfunction "F_9") (pintype "passive"))
      (node (ref "SEG2") (pin "9") (pinfunction "F_9") (pintype "passive"))
    )
    (net (code "48") (name "Net-(PAD13-P)") (class "Default")
      (node (ref "PAD13") (pin "1") (pinfunction "P_1") (pintype "passive"))
      (node (ref "PAD19") (pin "1") (pinfunction "P_1") (pintype "passive"))
      (node (ref "R8") (pin "2") (pinfunction "2_2") (pintype "passive"))
      (node (ref "SEG1") (pin "7") (pinfunction "A_7") (pintype "passive"))
      (node (ref "SEG2") (pin "7") (pinfunction "A_7") (pintype "passive"))
    )
    (net (code "49") (name "Net-(PAD14-P)") (class "Default")
      (node (ref "PAD14") (pin "1") (pinfunction "P_1") (pintype "passive"))
      (node (ref "PAD20") (pin "1") (pinfunction "P_1") (pintype "passive"))
      (node (ref "R7") (pin "2") (pinfunction "2_2") (pintype "passive"))
      (node (ref "SEG1") (pin "6") (pinfunction "B_6") (pintype "passive"))
      (node (ref "SEG2") (pin "6") (pinfunction "B_6") (pintype "passive"))
    )
    (net (code "50") (name "Net-(Q1-D)") (class "Default")
      (node (ref "Q1") (pin "3") (pinfunction "D_3") (pintype "passive"))
      (node (ref "R1") (pin "1") (pinfunction "1_1") (pintype "passive"))
    )
    (net (code "51") (name "Net-(Q2-D)") (class "Default")
      (node (ref "Q2") (pin "3") (pinfunction "D_3") (pintype "passive"))
      (node (ref "R2") (pin "1") (pinfunction "1_1") (pintype "passive"))
    )
    (net (code "52") (name "Net-(Q3-D)") (class "Default")
      (node (ref "Q3") (pin "3") (pinfunction "D_3") (pintype "passive"))
      (node (ref "R3") (pin "1") (pinfunction "1_1") (pintype "passive"))
    )
    (net (code "53") (name "Net-(Q4-D)") (class "Default")
      (node (ref "Q4") (pin "3") (pinfunction "D_3") (pintype "passive"))
      (node (ref "R4") (pin "1") (pinfunction "1_1") (pintype "passive"))
    )
    (net (code "54") (name "Net-(Q5-D)") (class "Default")
      (node (ref "Q5") (pin "3") (pinfunction "D_3") (pintype "passive"))
      (node (ref "R5") (pin "1") (pinfunction "1_1") (pintype "passive"))
    )
    (net (code "55") (name "Net-(Q6-D)") (class "Default")
      (node (ref "Q6") (pin "3") (pinfunction "D_3") (pintype "passive"))
      (node (ref "R6") (pin "1") (pinfunction "1_1") (pintype "passive"))
    )
    (net (code "56") (name "Net-(Q7-D)") (class "Default")
      (node (ref "Q7") (pin "3") (pinfunction "D_3") (pintype "passive"))
      (node (ref "R7") (pin "1") (pinfunction "1_1") (pintype "passive"))
    )
    (net (code "57") (name "Net-(Q8-D)") (class "Default")
      (node (ref "Q8") (pin "3") (pinfunction "D_3") (pintype "passive"))
      (node (ref "R8") (pin "1") (pinfunction "1_1") (pintype "passive"))
    )
    (net (code "58") (name "Net-(Q10-D)") (class "Default")
      (node (ref "Q10") (pin "3") (pinfunction "D_3") (pintype "passive"))
      (node (ref "Q9") (pin "1") (pinfunction "G_1") (pintype "passive"))
      (node (ref "R9") (pin "2") (pinfunction "2_2") (pintype "passive"))
    )
    (net (code "59") (name "Net-(Q11-G)") (class "Default")
      (node (ref "Q11") (pin "1") (pinfunction "G_1") (pintype "passive"))
      (node (ref "Q12") (pin "3") (pinfunction "D_3") (pintype "passive"))
      (node (ref "R10") (pin "2") (pinfunction "2_2") (pintype "passive"))
    )
    (net (code "60") (name "Net-(Q13-G)") (class "Default")
      (node (ref "Q13") (pin "1") (pinfunction "G_1") (pintype "passive"))
      (node (ref "Q14") (pin "3") (pinfunction "D_3") (pintype "passive"))
      (node (ref "R11") (pin "2") (pinfunction "2_2") (pintype "passive"))
    )
    (net (code "61") (name "Net-(Q15-G)") (class "Default")
      (node (ref "Q15") (pin "1") (pinfunction "G_1") (pintype "passive"))
      (node (ref "Q16") (pin "3") (pinfunction "D_3") (pintype "passive"))
      (node (ref "R12") (pin "2") (pinfunction "2_2") (pintype "passive"))
    )
    (net (code "62") (name "Net-(Q17-G)") (class "Default")
      (node (ref "D2") (pin "A") (pinfunction "A_A") (pintype "passive"))
      (node (ref "Q17") (pin "1") (pinfunction "G_1") (pintype "passive"))
      (node (ref "Q18") (pin "C") (pinfunction "C_C") (pintype "passive"))
      (node (ref "R19") (pin "2") (pinfunction "2_2") (pintype "passive"))
    )
    (net (code "63") (name "Net-(Q18-PadB)") (class "Default")
      (node (ref "Q18") (pin "B") (pinfunction "B_B") (pintype "passive"))
      (node (ref "Q19") (pin "C") (pinfunction "C_C") (pintype "passive"))
      (node (ref "R18") (pin "1") (pinfunction "1_1") (pintype "passive"))
    )
    (net (code "64") (name "Net-(Q19-PadB)") (class "Default")
      (node (ref "Q19") (pin "B") (pinfunction "B_B") (pintype "passive"))
      (node (ref "R20") (pin "1") (pinfunction "1_1") (pintype "passive"))
    )
    (net (code "65") (name "RFM69_DIO0") (class "Default")
      (node (ref "IC1") (pin "25") (pinfunction "PB12_25") (pintype "bidirectional"))
      (node (ref "U$1") (pin "DIO0") (pinfunction "DIO0_DIO0") (pintype "bidirectional"))
    )
    (net (code "66") (name "RFM69_DIO1") (class "Default")
      (node (ref "IC1") (pin "26") (pinfunction "PB13_26") (pintype "bidirectional"))
      (node (ref "U$1") (pin "DIO1") (pinfunction "DIO1_DIO1") (pintype "bidirectional"))
    )
    (net (code "67") (name "RFM69_DIO2") (class "Default")
      (node (ref "IC1") (pin "27") (pinfunction "PB14_27") (pintype "bidirectional"))
      (node (ref "U$1") (pin "DIO2") (pinfunction "DIO2_DIO2") (pintype "bidirectional"))
    )
    (net (code "68") (name "RFM69_DIO3") (class "Default")
      (node (ref "IC1") (pin "28") (pinfunction "PB15_28") (pintype "bidirectional"))
      (node (ref "U$1") (pin "DIO3") (pinfunction "DIO3_DIO3") (pintype "bidirectional"))
    )
    (net (code "69") (name "RFM69_DIO4") (class "Default")
      (node (ref "IC1") (pin "29") (pinfunction "PA8_29") (pintype "bidirectional"))
      (node (ref "U$1") (pin "DIO4") (pinfunction "DIO4_DIO4") (pintype "bidirectional"))
    )
    (net (code "70") (name "RFM69_DIO5") (class "Default")
      (node (ref "IC1") (pin "30") (pinfunction "PA9_30") (pintype "bidirectional"))
      (node (ref "U$1") (pin "DIO5") (pinfunction "DIO5_DIO5") (pintype "bidirectional"))
    )
    (net (code "71") (name "SCK") (class "Default")
      (node (ref "IC1") (pin "39") (pinfunction "PB3_39") (pintype "bidirectional"))
      (node (ref "M1") (pin "5") (pinfunction "SCK_5") (pintype "bidirectional"))
      (node (ref "U$1") (pin "SCK") (pinfunction "SCK_SCK") (pintype "bidirectional"))
    )
    (net (code "72") (name "SWITCH") (class "Default")
      (node (ref "D2") (pin "C") (pinfunction "C_C") (pintype "passive"))
      (node (ref "IC1") (pin "3") (pinfunction "PC14_3") (pintype "bidirectional"))
      (node (ref "S4") (pin "2") (pinfunction "S_2") (pintype "passive"))
    )
    (net (code "73") (name "S_A") (class "Default")
      (node (ref "IC1") (pin "19") (pinfunction "PB1_19") (pintype "bidirectional"))
      (node (ref "Q8") (pin "1") (pinfunction "G_1") (pintype "passive"))
    )
    (net (code "74") (name "S_B") (class "Default")
      (node (ref "IC1") (pin "20") (pinfunction "PB2_20") (pintype "bidirectional"))
      (node (ref "Q7") (pin "1") (pinfunction "G_1") (pintype "passive"))
    )
    (net (code "75") (name "S_C") (class "Default")
      (node (ref "IC1") (pin "35") (pinfunction "PF6_35") (pintype "bidirectional"))
      (node (ref "Q5") (pin "1") (pinfunction "G_1") (pintype "passive"))
    )
    (net (code "76") (name "S_D") (class "Default")
      (node (ref "IC1") (pin "45") (pinfunction "PB8_45") (pintype "bidirectional"))
      (node (ref "Q6") (pin "1") (pinfunction "G_1") (pintype "passive"))
    )
    (net (code "77") (name "S_DOT") (class "Default")
      (node (ref "IC1") (pin "38") (pinfunction "PA15_38") (pintype "bidirectional"))
      (node (ref "Q4") (pin "1") (pinfunction "G_1") (pintype "passive"))
    )
    (net (code "78") (name "S_E") (class "Default")
      (node (ref "IC1") (pin "46") (pinfunction "PB9_46") (pintype "bidirectional"))
      (node (ref "Q1") (pin "1") (pinfunction "G_1") (pintype "passive"))
    )
    (net (code "79") (name "S_F") (class "Default")
      (node (ref "IC1") (pin "18") (pinfunction "PB0_18") (pintype "bidirectional"))
      (node (ref "Q3") (pin "1") (pinfunction "G_1") (pintype "passive"))
    )
    (net (code "80") (name "S_G") (class "Default")
      (node (ref "IC1") (pin "17") (pinfunction "PA7_17") (pintype "bidirectional"))
      (node (ref "Q2") (pin "1") (pinfunction "G_1") (pintype "passive"))
    )
    (net (code "81") (name "V+") (class "Default")
      (node (ref "BAT1") (pin "+") (pinfunction "+_+") (pintype "passive"))
      (node (ref "C9") (pin "1") (pinfunction "1_1") (pintype "passive"))
      (node (ref "IC3") (pin "3") (pinfunction "VBAT_3") (pintype "bidirectional"))
      (node (ref "Q17") (pin "2") (pinfunction "S_2") (pintype "passive"))
      (node (ref "R19") (pin "1") (pinfunction "1_1") (pintype "passive"))
    )
    (net (code "82") (name "VCC") (class "Default")
      (node (ref "C13") (pin "1") (pinfunction "1_1") (pintype "passive"))
      (node (ref "C7") (pin "+") (pinfunction "+_+") (pintype "passive"))
      (node (ref "IC4") (pin "1") (pinfunction "VIN_1") (pintype "power_in"))
      (node (ref "L3") (pin "1") (pinfunction "1_1") (pintype "passive"))
      (node (ref "Q17") (pin "3") (pinfunction "D_3") (pintype "passive"))
      (node (ref "R13") (pin "2") (pinfunction "2_2") (pintype "passive"))
      (node (ref "R18") (pin "2") (pinfunction "2_2") (pintype "passive"))
      (node (ref "R23") (pin "1") (pinfunction "1_1") (pintype "passive"))
    )
    (net (code "83") (name "VDD") (class "Default")
      (node (ref "C1") (pin "1") (pinfunction "1_1") (pintype "passive"))
      (node (ref "C14") (pin "1") (pinfunction "1_1") (pintype "passive"))
      (node (ref "C2") (pin "1") (pinfunction "1_1") (pintype "passive"))
      (node (ref "IC1") (pin "1") (pinfunction "VDD_1") (pintype "power_in"))
      (node (ref "IC1") (pin "24") (pinfunction "VDD_24") (pintype "power_in"))
      (node (ref "IC1") (pin "48") (pinfunction "VDD_48") (pintype "power_in"))
      (node (ref "IC4") (pin "5") (pinfunction "VOUT_5") (pintype "output"))
      (node (ref "L2") (pin "1") (pinfunction "1_1") (pintype "passive"))
      (node (ref "M1") (pin "2") (pinfunction "VCC_2") (pintype "power_in"))
      (node (ref "SWD") (pin "1") (pinfunction "1_1") (pintype "passive"))
      (node (ref "U$1") (pin "VCC") (pinfunction "VCC_VCC") (pintype "bidirectional"))
    )
    (net (code "84") (name "unconnected-(PAD1-P-Pad1)") (class "Default")
      (node (ref "PAD1") (pin "1") (pinfunction "P_1") (pintype "passive"))
    )
    (net (code "85") (name "unconnected-(PAD2-P-Pad1)") (class "Default")
      (node (ref "PAD2") (pin "1") (pinfunction "P_1") (pintype "passive"))
    )
    (net (code "86") (name "unconnected-(SEG1-COM-Pad3)") (class "Default")
      (node (ref "SEG1") (pin "3") (pinfunction "COM_3") (pintype "passive"))
    )
    (net (code "87") (name "unconnected-(SEG2-COM-Pad3)") (class "Default")
      (node (ref "SEG2") (pin "3") (pinfunction "COM_3") (pintype "passive"))
    )
    (net (code "88") (name "unconnected-(U$1-PadNC)") (class "Default")
      (node (ref "U$1") (pin "NC") (pinfunction "NC_NC") (pintype "bidirectional"))
    )
    (net (code "89") (name "unconnected-(U$1-PadRESET)") (class "Default")
      (node (ref "U$1") (pin "RESET") (pinfunction "RESET_RESET") (pintype "bidirectional"))
    )
    (net (code "90") (name "unconnected-(X1-Pad2)") (class "Default")
      (node (ref "X1") (pin "2") (pinfunction "2_2") (pintype "input"))
    )
    (net (code "91") (name "unconnected-(X1-Pad3)") (class "Default")
      (node (ref "X1") (pin "3") (pinfunction "3_3") (pintype "input"))
    )
    (net (code "92") (name "unconnected-(X1-Pad4)") (class "Default")
      (node (ref "X1") (pin "4") (pinfunction "4_4") (pintype "input"))
    )
  )
)
